# ESP32.net
KiCad netlist of a schematic drawn in Altium Designer
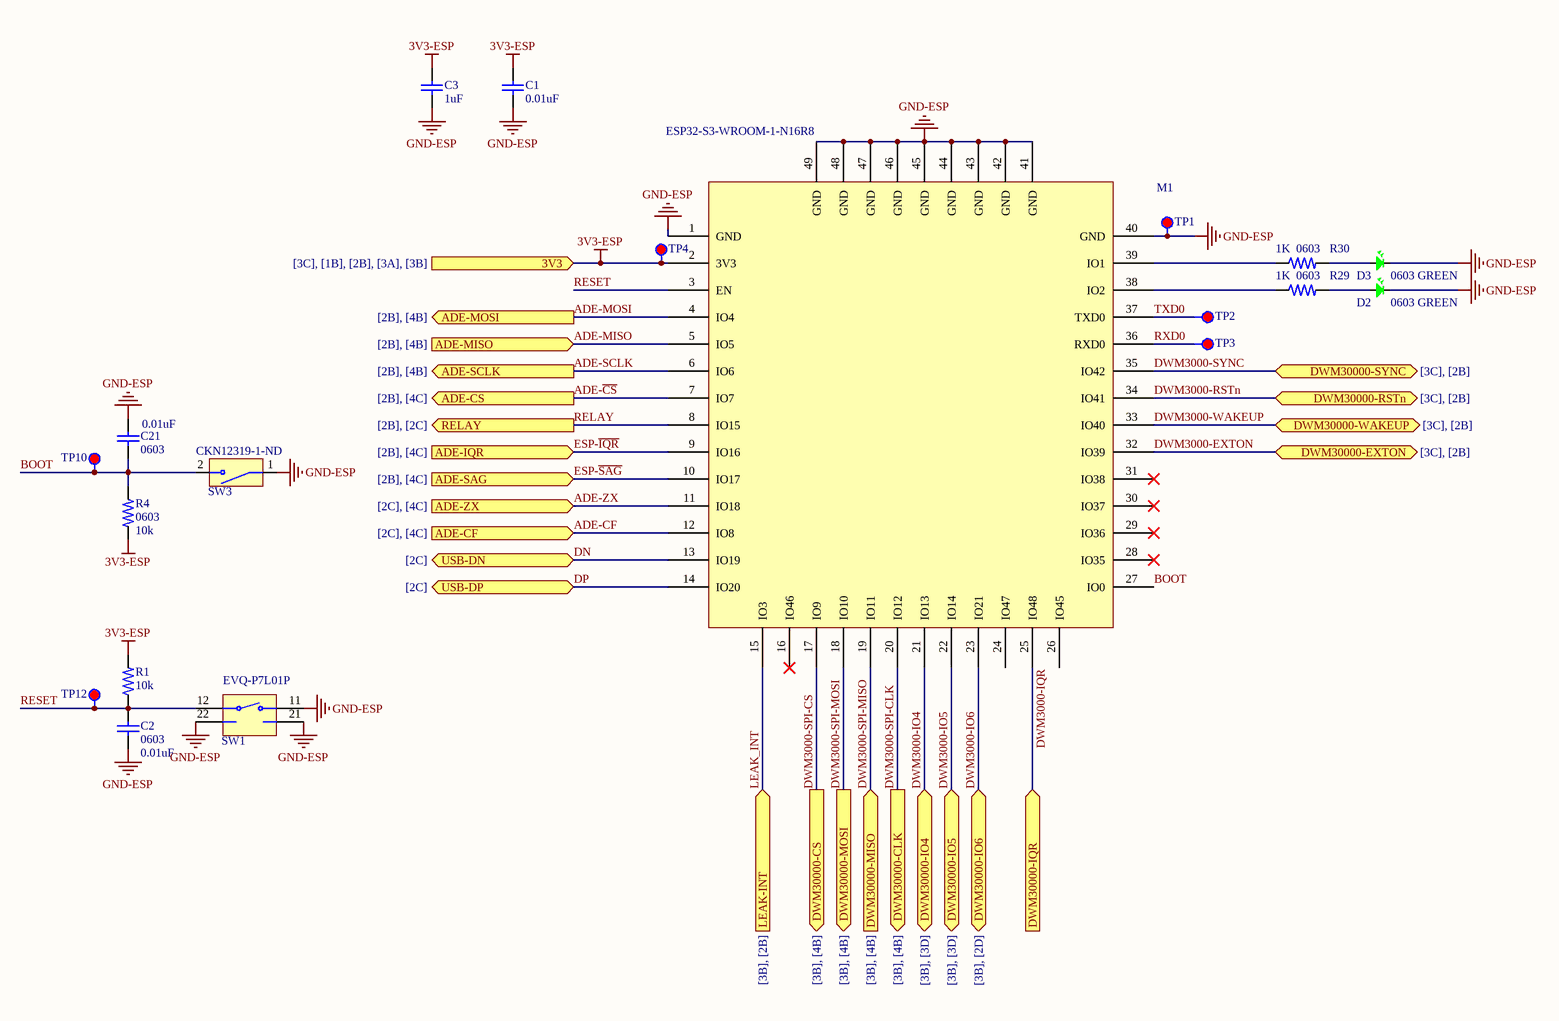
[diagram p0: ESP32.SchDoc]

(export (version "E")
  (design (tool "Eeschema 10.0.6"))
  (components
    (comp (ref "C1")
      (value "0.01uF")
      (footprint "SMD-CAP-0603-YAGEO")
      (description "Multilayer Ceramic Capacitor, 0.1 uF, 10 V, ± 10%, X7R, 0603 [1608 Metric]")
      (fields
        (field (name "MANUFACTURER") "Yageo")
        (field (name "MANUFACTURER PART NUMBER") "CC0603KRX7R6BB104")
        (field (name "DESIGNER") "TVBac")
      )
      (libsource (lib "Capacitors") (part "CAP; 0.1uF; 10V; 0603; SMD; CC0603KRX7R6BB104"))
    )
    (comp (ref "C2")
      (value "0.01uF")
      (footprint "SMD-CAP-0603-YAGEO")
      (description "Multilayer Ceramic Capacitor, 0.01 uF, 16 V, ± 10%, X7R, 0603 [1608 Metric]")
      (fields
        (field (name "MANUFACTURER") "Yageo")
        (field (name "MANUFACTURER PART NUMBER") "CC0603KRX7R7BB103")
        (field (name "PACKAGE") "0603")
        (field (name "DESIGNER") "TVBac")
      )
      (libsource (lib "Capacitors") (part "CAP; 0.01uF; 16V; 0603; SMD; CC0603KRX7R7BB103"))
    )
    (comp (ref "C3")
      (value "1uF")
      (footprint "SMD-CAP-0603-YAGEO")
      (description "0603 1 uF 16 V ±10 % Tolerance X7R SMT Multilayer Ceramic Capacitor")
      (fields
        (field (name "MANUFACTURER") "Yageo")
        (field (name "MANUFACTURER PART NUMBER") "CC0603KRX7R7BB105")
        (field (name "DESIGNER") "TVBac")
      )
      (libsource (lib "Capacitors") (part "CAP; 1uF; 16V; 0603; SMD; CC0603KRX7R7BB105"))
    )
    (comp (ref "C21")
      (value "0.01uF")
      (footprint "SMD-CAP-0603-YAGEO")
      (description "Multilayer Ceramic Capacitor, 0.01 uF, 16 V, ± 10%, X7R, 0603 [1608 Metric]")
      (fields
        (field (name "MANUFACTURER") "Yageo")
        (field (name "MANUFACTURER PART NUMBER") "CC0603KRX7R7BB103")
        (field (name "PACKAGE") "0603")
        (field (name "DESIGNER") "TVBac")
      )
      (libsource (lib "Capacitors") (part "CAP; 0.01uF; 16V; 0603; SMD; CC0603KRX7R7BB103"))
    )
    (comp (ref "D2")
      (value "0603 GREEN")
      (footprint "LED0603_GREEN")
      (fields
        (field (name "MANUFACTURER") "Amicc")
        (field (name "MANUFACTURE PART NUMBER") "A-SP192DGHC-C01-4T")
      )
      (libsource (lib "LED") (part "L0603_GREEN"))
    )
    (comp (ref "D3")
      (value "0603 GREEN")
      (footprint "LED0603_GREEN")
      (fields
        (field (name "MANUFACTURER") "Amicc")
        (field (name "MANUFACTURE PART NUMBER") "A-SP192DGHC-C01-4T")
      )
      (libsource (lib "LED") (part "L0603_GREEN"))
    )
    (comp (ref "M1")
      (value "Bluetooth, WiFi 802.11b/g/n, Bluetooth v4.2 +EDR Transceiver Module 2.4GHz ~ 2.5GHz PCB Trace Surface Mount")
      (footprint "MODULE-ESP32-S3-WROOM-1-N16R8")
      (description "SMD mod, ESP32-S3R8 with 3.3V, 8MB Octal PSRAM die insid, 6MBQuad SPI flash, pcb ant")
      (fields
        (field (name "MANUFACTURER") "Espressif Systems")
        (field (name "MANUFACTURER PART NUMBER") "ESP32-S3-WROOM-1-N16R8")
        (field (name "DESIGNER") "TVBac")
      )
      (libsource (lib "Modules") (part "ESP32-S3-WROOM-1-N16R8; SMD;"))
    )
    (comp (ref "R1")
      (value "10k")
      (footprint "SMD-RES-0603-SEI")
      (description "SMD Chip Resistor, 10 kOhm, ± 1%, 250 mW, 0603 [1608 Metric], Thick Film, Anti-Surge")
      (fields
        (field (name "MANUFACTURER") "Rohm")
        (field (name "MANUFACTURER PART NUMBER") "ESR03EZPF1002")
        (field (name "DESIGNER") "TVBac")
      )
      (libsource (lib "Smartsocket") (part "RES; 10K; 0603; SMD; ESR03EZPF1002"))
    )
    (comp (ref "R4")
      (value "10k")
      (footprint "SMD-RES-0603-SEI")
      (description "SMD Chip Resistor, 10 kOhm, ± 1%, 250 mW, 0603 [1608 Metric], Thick Film, Anti-Surge")
      (fields
        (field (name "MANUFACTURER") "Rohm")
        (field (name "MANUFACTURER PART NUMBER") "ESR03EZPF1002")
        (field (name "PACKAGE") "0603")
        (field (name "DESIGNER") "TVBac")
      )
      (libsource (lib "Resistors") (part "RES; 10K; 0603; SMD; ESR03EZPF1002"))
    )
    (comp (ref "R29")
      (value "1K")
      (footprint "SMD-RES-0603-SEI")
      (description "SMD Chip Resistor, 1 kOhm, ± 1%, 250 mW, 0603 [1608 Metric], Thick Film, Anti-Surge")
      (fields
        (field (name "MANUFACTURER") "Rohm")
        (field (name "MANUFACTURER PART NUMBER") "ESR03EZPF1001")
        (field (name "PACKAGE") "0603")
        (field (name "DESIGNER") "TVBac")
      )
      (libsource (lib "Resistors") (part "RES; 1K; 0603; SMD; ESR03EZPF1001"))
    )
    (comp (ref "R30")
      (value "1K")
      (footprint "SMD-RES-0603-SEI")
      (description "SMD Chip Resistor, 1 kOhm, ± 1%, 250 mW, 0603 [1608 Metric], Thick Film, Anti-Surge")
      (fields
        (field (name "MANUFACTURER") "Rohm")
        (field (name "MANUFACTURER PART NUMBER") "ESR03EZPF1001")
        (field (name "PACKAGE") "0603")
        (field (name "DESIGNER") "TVBac")
      )
      (libsource (lib "Resistors") (part "RES; 1K; 0603; SMD; ESR03EZPF1001"))
    )
    (comp (ref "SW1")
      (value "https://www.digikey.com/en/products/detail/panasonic-electronic-components/EVQ-P7L01P/4429453")
      (footprint "SW-HxLxW-1.1x3.5x2.9-PEC")
      (description "Tactile Switch SPST-NO Side Actuated Surface Mount, Right Angle")
      (fields
        (field (name "MP") "EVQ-P7L01P")
        (field (name "MF") "Panasonic Electronic Components")
        (field (name "DIGI-KEY_PART_NUMBER") "P16769TR-ND")
      )
      (libsource (lib "Button") (part "BUT; SW; SMD; EVQ-P7L01P"))
    )
    (comp (ref "SW3")
      (value "Tactile Switch SPST-NO Top Actuated Surface Mount")
      (footprint "SW-HxLxW-5.0x6.0x3.5-C&K")
      (description "Switch Tactile N.O. SPST Rectangular Button J-Bend 0.05A 12VDC 1.77N SMD T/R")
      (fields
        (field (name "SUPPLIER PART NUMBER") "CKN12319-1-ND")
        (field (name "MANUFACTURER") "ITT C&K")
        (field (name "MANUFACTURER PART NUMBER") "PTS636SM50JSMTRLFS")
      )
      (libsource (lib "Button") (part "BUT; SW; SMD; PTS636SM50JSMTRLFS"))
    )
    (comp (ref "TP1")
      (value "Test Point")
      (footprint "TEST_POINT")
      (libsource (lib "Socket") (part "TEST_POINT"))
    )
    (comp (ref "TP2")
      (value "Test Point")
      (footprint "TEST_POINT")
      (libsource (lib "Socket") (part "TEST_POINT"))
    )
    (comp (ref "TP3")
      (value "Test Point")
      (footprint "TEST_POINT")
      (libsource (lib "Socket") (part "TEST_POINT"))
    )
    (comp (ref "TP4")
      (value "Test Point")
      (footprint "TEST_POINT")
      (libsource (lib "Socket") (part "TEST_POINT"))
    )
    (comp (ref "TP10")
      (value "Test Point")
      (footprint "TEST_POINT")
      (libsource (lib "Socket") (part "TEST_POINT"))
    )
    (comp (ref "TP12")
      (value "Test Point")
      (footprint "TEST_POINT")
      (libsource (lib "Socket") (part "TEST_POINT"))
    )
  )
  (nets
    (net (code "1") (name "/ADE-CF") (class "Default")
      (node (ref "M1") (pin "12") (pinfunction "IO8_12") (pintype "passive"))
    )
    (net (code "2") (name "/ADE-MISO") (class "Default")
      (node (ref "M1") (pin "5") (pinfunction "IO5_5") (pintype "passive"))
    )
    (net (code "3") (name "/ADE-MOSI") (class "Default")
      (node (ref "M1") (pin "4") (pinfunction "IO4_4") (pintype "passive"))
    )
    (net (code "4") (name "/ADE-SCLK") (class "Default")
      (node (ref "M1") (pin "6") (pinfunction "IO6_6") (pintype "passive"))
    )
    (net (code "5") (name "/ADE-ZX") (class "Default")
      (node (ref "M1") (pin "11") (pinfunction "IO18_11") (pintype "passive"))
    )
    (net (code "6") (name "/ADE-~{CS}") (class "Default")
      (node (ref "M1") (pin "7") (pinfunction "IO7_7") (pintype "passive"))
    )
    (net (code "7") (name "/BOOT") (class "Default")
      (node (ref "C21") (pin "2") (pinfunction "2_2") (pintype "passive"))
      (node (ref "M1") (pin "27") (pinfunction "IO0_27") (pintype "passive"))
      (node (ref "R4") (pin "1") (pinfunction "1_1") (pintype "passive"))
      (node (ref "SW3") (pin "2") (pinfunction "NO_2") (pintype "passive"))
      (node (ref "TP10") (pin "1") (pinfunction "1_1") (pintype "passive"))
    )
    (net (code "8") (name "/DN") (class "Default")
      (node (ref "M1") (pin "13") (pinfunction "IO19_13") (pintype "passive"))
    )
    (net (code "9") (name "/DP") (class "Default")
      (node (ref "M1") (pin "14") (pinfunction "IO20_14") (pintype "passive"))
    )
    (net (code "10") (name "/DWM3000-EXTON") (class "Default")
      (node (ref "M1") (pin "32") (pinfunction "IO39_32") (pintype "passive"))
    )
    (net (code "11") (name "/DWM3000-IO4") (class "Default")
      (node (ref "M1") (pin "21") (pinfunction "IO13_21") (pintype "passive"))
    )
    (net (code "12") (name "/DWM3000-IO5") (class "Default")
      (node (ref "M1") (pin "22") (pinfunction "IO14_22") (pintype "passive"))
    )
    (net (code "13") (name "/DWM3000-IO6") (class "Default")
      (node (ref "M1") (pin "23") (pinfunction "IO21_23") (pintype "passive"))
    )
    (net (code "14") (name "/DWM3000-IQR") (class "Default")
      (node (ref "M1") (pin "25") (pinfunction "IO48_25") (pintype "passive"))
    )
    (net (code "15") (name "/DWM3000-RSTn") (class "Default")
      (node (ref "M1") (pin "34") (pinfunction "IO41_34") (pintype "passive"))
    )
    (net (code "16") (name "/DWM3000-SPI-CLK") (class "Default")
      (node (ref "M1") (pin "20") (pinfunction "IO12_20") (pintype "passive"))
    )
    (net (code "17") (name "/DWM3000-SPI-CS") (class "Default")
      (node (ref "M1") (pin "17") (pinfunction "IO9_17") (pintype "passive"))
    )
    (net (code "18") (name "/DWM3000-SPI-MISO") (class "Default")
      (node (ref "M1") (pin "19") (pinfunction "IO11_19") (pintype "passive"))
    )
    (net (code "19") (name "/DWM3000-SPI-MOSI") (class "Default")
      (node (ref "M1") (pin "18") (pinfunction "IO10_18") (pintype "passive"))
    )
    (net (code "20") (name "/DWM3000-SYNC") (class "Default")
      (node (ref "M1") (pin "35") (pinfunction "IO42_35") (pintype "passive"))
    )
    (net (code "21") (name "/DWM3000-WAKEUP") (class "Default")
      (node (ref "M1") (pin "33") (pinfunction "IO40_33") (pintype "passive"))
    )
    (net (code "22") (name "/ESP-~{IQR}") (class "Default")
      (node (ref "M1") (pin "9") (pinfunction "IO16_9") (pintype "passive"))
    )
    (net (code "23") (name "/ESP-~{SAG}") (class "Default")
      (node (ref "M1") (pin "10") (pinfunction "IO17_10") (pintype "passive"))
    )
    (net (code "24") (name "/LEAK_INT") (class "Default")
      (node (ref "M1") (pin "15") (pinfunction "IO3_15") (pintype "passive"))
    )
    (net (code "25") (name "/RELAY") (class "Default")
      (node (ref "M1") (pin "8") (pinfunction "IO15_8") (pintype "passive"))
    )
    (net (code "26") (name "/RESET") (class "Default")
      (node (ref "C2") (pin "2") (pinfunction "2_2") (pintype "passive"))
      (node (ref "M1") (pin "3") (pinfunction "EN_3") (pintype "passive"))
      (node (ref "R1") (pin "1") (pinfunction "1_1") (pintype "passive"))
      (node (ref "SW1") (pin "12") (pinfunction "2_12") (pintype "passive"))
      (node (ref "TP12") (pin "1") (pinfunction "1_1") (pintype "passive"))
    )
    (net (code "27") (name "/RXD0") (class "Default")
      (node (ref "M1") (pin "36") (pinfunction "RXD0_36") (pintype "passive"))
      (node (ref "TP3") (pin "1") (pinfunction "1_1") (pintype "passive"))
    )
    (net (code "28") (name "/TXD0") (class "Default")
      (node (ref "M1") (pin "37") (pinfunction "TXD0_37") (pintype "passive"))
      (node (ref "TP2") (pin "1") (pinfunction "1_1") (pintype "passive"))
    )
    (net (code "29") (name "3V3-ESP") (class "Default")
      (node (ref "C1") (pin "2") (pinfunction "2_2") (pintype "passive"))
      (node (ref "C3") (pin "2") (pinfunction "2_2") (pintype "passive"))
      (node (ref "M1") (pin "2") (pinfunction "3V3_2") (pintype "passive"))
      (node (ref "R1") (pin "2") (pinfunction "2_2") (pintype "passive"))
      (node (ref "R4") (pin "2") (pinfunction "2_2") (pintype "passive"))
      (node (ref "TP4") (pin "1") (pinfunction "1_1") (pintype "passive"))
    )
    (net (code "30") (name "GND-ESP") (class "Default")
      (node (ref "C1") (pin "1") (pinfunction "1_1") (pintype "passive"))
      (node (ref "C2") (pin "1") (pinfunction "1_1") (pintype "passive"))
      (node (ref "C21") (pin "1") (pinfunction "1_1") (pintype "passive"))
      (node (ref "C3") (pin "1") (pinfunction "1_1") (pintype "passive"))
      (node (ref "D2") (pin "2") (pinfunction "2_2") (pintype "passive"))
      (node (ref "D3") (pin "2") (pinfunction "2_2") (pintype "passive"))
      (node (ref "M1") (pin "1") (pinfunction "GND_1") (pintype "passive"))
      (node (ref "M1") (pin "40") (pinfunction "GND_40") (pintype "passive"))
      (node (ref "M1") (pin "41") (pinfunction "GND_41") (pintype "passive"))
      (node (ref "M1") (pin "42") (pinfunction "GND_42") (pintype "passive"))
      (node (ref "M1") (pin "43") (pinfunction "GND_43") (pintype "passive"))
      (node (ref "M1") (pin "44") (pinfunction "GND_44") (pintype "passive"))
      (node (ref "M1") (pin "45") (pinfunction "GND_45") (pintype "passive"))
      (node (ref "M1") (pin "46") (pinfunction "GND_46") (pintype "passive"))
      (node (ref "M1") (pin "47") (pinfunction "GND_47") (pintype "passive"))
      (node (ref "M1") (pin "48") (pinfunction "GND_48") (pintype "passive"))
      (node (ref "M1") (pin "49") (pinfunction "GND_49") (pintype "passive"))
      (node (ref "SW1") (pin "11") (pinfunction "1_11") (pintype "passive"))
      (node (ref "SW1") (pin "21") (pinfunction "1_21") (pintype "passive"))
      (node (ref "SW1") (pin "22") (pinfunction "2_22") (pintype "passive"))
      (node (ref "SW3") (pin "1") (pinfunction "COM_1") (pintype "passive"))
      (node (ref "TP1") (pin "1") (pinfunction "1_1") (pintype "passive"))
    )
    (net (code "31") (name "Net-(D2-Pad1)") (class "Default")
      (node (ref "D2") (pin "1") (pinfunction "1_1") (pintype "passive"))
      (node (ref "R29") (pin "2") (pinfunction "2_2") (pintype "passive"))
    )
    (net (code "32") (name "Net-(D3-Pad1)") (class "Default")
      (node (ref "D3") (pin "1") (pinfunction "1_1") (pintype "passive"))
      (node (ref "R30") (pin "2") (pinfunction "2_2") (pintype "passive"))
    )
    (net (code "33") (name "Net-(M1-IO1)") (class "Default")
      (node (ref "M1") (pin "39") (pinfunction "IO1_39") (pintype "passive"))
      (node (ref "R30") (pin "1") (pinfunction "1_1") (pintype "passive"))
    )
    (net (code "34") (name "Net-(M1-IO2)") (class "Default")
      (node (ref "M1") (pin "38") (pinfunction "IO2_38") (pintype "passive"))
      (node (ref "R29") (pin "1") (pinfunction "1_1") (pintype "passive"))
    )
    (net (code "35") (name "unconnected-(M1-IO35-Pad28)") (class "Default")
      (node (ref "M1") (pin "28") (pinfunction "IO35_28") (pintype "passive+no_connect"))
    )
    (net (code "36") (name "unconnected-(M1-IO36-Pad29)") (class "Default")
      (node (ref "M1") (pin "29") (pinfunction "IO36_29") (pintype "passive+no_connect"))
    )
    (net (code "37") (name "unconnected-(M1-IO37-Pad30)") (class "Default")
      (node (ref "M1") (pin "30") (pinfunction "IO37_30") (pintype "passive+no_connect"))
    )
    (net (code "38") (name "unconnected-(M1-IO38-Pad31)") (class "Default")
      (node (ref "M1") (pin "31") (pinfunction "IO38_31") (pintype "passive+no_connect"))
    )
    (net (code "39") (name "unconnected-(M1-IO45-Pad26)") (class "Default")
      (node (ref "M1") (pin "26") (pinfunction "IO45_26") (pintype "passive"))
    )
    (net (code "40") (name "unconnected-(M1-IO46-Pad16)") (class "Default")
      (node (ref "M1") (pin "16") (pinfunction "IO46_16") (pintype "passive+no_connect"))
    )
    (net (code "41") (name "unconnected-(M1-IO47-Pad24)") (class "Default")
      (node (ref "M1") (pin "24") (pinfunction "IO47_24") (pintype "passive"))
    )
  )
)
